# Electric_Imp_imp002_Breakout.net
KiCad netlist of a schematic drawn in EAGLE
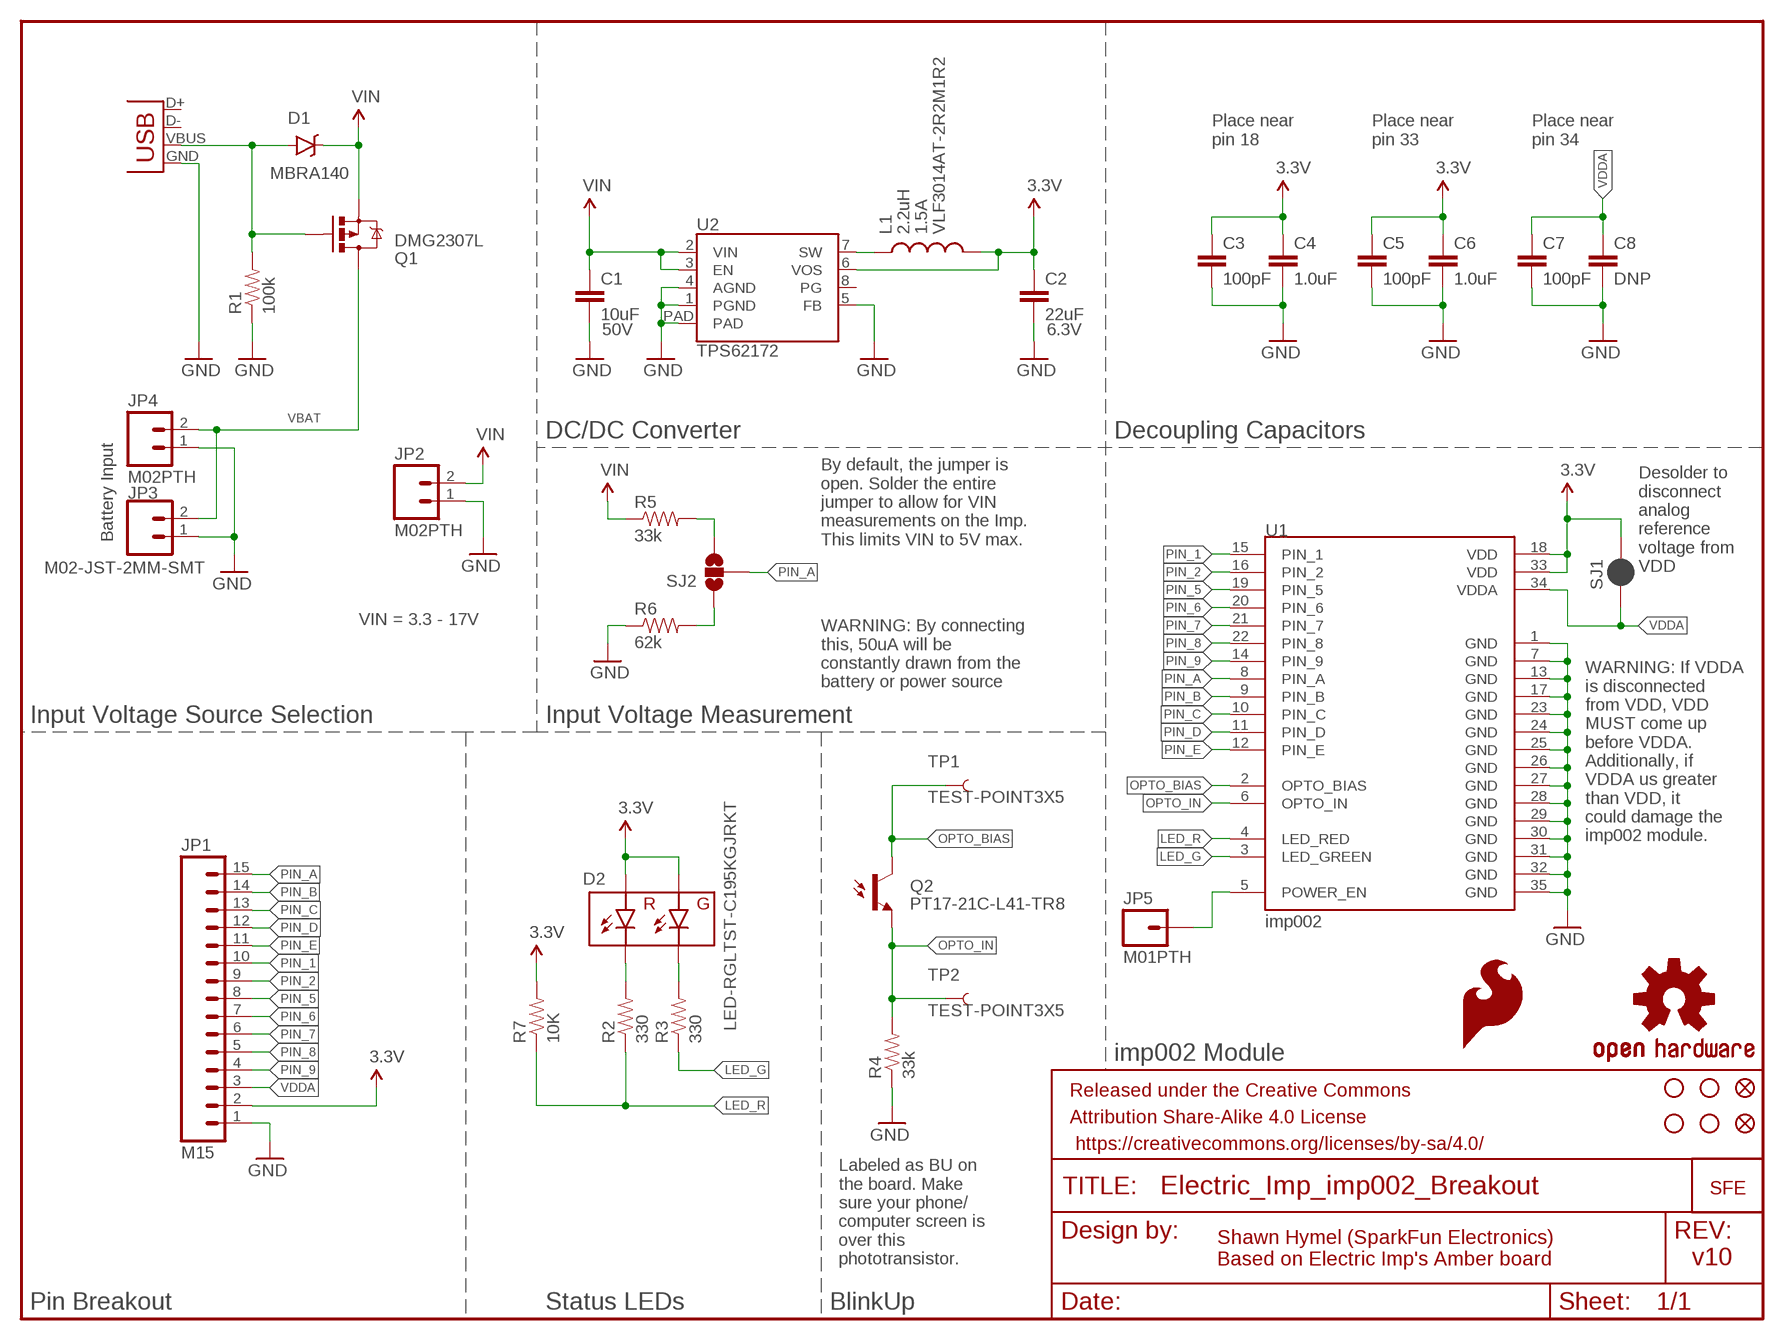
[diagram p0: schematic, sheet 1]

(export (version "E")
  (design (tool "Eeschema 10.0.6"))
  (components
    (comp (ref "C1")
      (value "10uF")
      (footprint "eagle-import:1210")
      (libsource (lib "eagle-import") (part "SparkFun-Passives_CAP1210"))
    )
    (comp (ref "C2")
      (value "22uF")
      (footprint "eagle-import:0805")
      (libsource (lib "eagle-import") (part "SparkFun-Passives_CAP0805"))
    )
    (comp (ref "C3")
      (value "100pF")
      (footprint "eagle-import:0603-CAP")
      (libsource (lib "eagle-import") (part "CAP0603-CAP"))
    )
    (comp (ref "C4")
      (value "1.0uF")
      (footprint "eagle-import:0603-CAP")
      (libsource (lib "eagle-import") (part "1.0UF-16V-10%(0603)"))
    )
    (comp (ref "C5")
      (value "100pF")
      (footprint "eagle-import:0603-CAP")
      (libsource (lib "eagle-import") (part "CAP0603-CAP"))
    )
    (comp (ref "C6")
      (value "1.0uF")
      (footprint "eagle-import:0603-CAP")
      (libsource (lib "eagle-import") (part "1.0UF-16V-10%(0603)"))
    )
    (comp (ref "C7")
      (value "100pF")
      (footprint "eagle-import:0603-CAP")
      (libsource (lib "eagle-import") (part "CAP0603-CAP"))
    )
    (comp (ref "C8")
      (value "DNP")
      (footprint "eagle-import:0603-CAP")
      (libsource (lib "eagle-import") (part "CAP0603-CAP"))
    )
    (comp (ref "D1")
      (value "MBRA140")
      (footprint "eagle-import:SMA-DIODE")
      (libsource (lib "eagle-import") (part "DIODE-SCHOTTKY-MBRA140"))
    )
    (comp (ref "D2")
      (value "LED-RGLTST-C195KGJRKT")
      (footprint "eagle-import:LTST-C195KGJRKT")
      (libsource (lib "eagle-import") (part "LED-RGLTST-C195KGJRKT"))
    )
    (comp (ref "FID1")
      (value "FIDUCIAL1X2")
      (footprint "eagle-import:FIDUCIAL-1X2")
      (libsource (lib "eagle-import") (part "FIDUCIAL1X2"))
    )
    (comp (ref "FID2")
      (value "FIDUCIAL1X2")
      (footprint "eagle-import:FIDUCIAL-1X2")
      (libsource (lib "eagle-import") (part "FIDUCIAL1X2"))
    )
    (comp (ref "FRAME1")
      (value "FRAME-LETTER")
      (footprint "eagle-import:CREATIVE_COMMONS")
      (libsource (lib "eagle-import") (part "FRAME-LETTER"))
    )
    (comp (ref "JP1")
      (value "M15")
      (footprint "eagle-import:1X15")
      (libsource (lib "eagle-import") (part "M15"))
    )
    (comp (ref "JP2")
      (value "M02PTH")
      (footprint "eagle-import:1X02")
      (libsource (lib "eagle-import") (part "M02PTH"))
    )
    (comp (ref "JP3")
      (value "M02-JST-2MM-SMT")
      (footprint "eagle-import:JST-2-SMD")
      (libsource (lib "eagle-import") (part "M02-JST-2MM-SMT"))
    )
    (comp (ref "JP4")
      (value "M02PTH")
      (footprint "eagle-import:1X02")
      (libsource (lib "eagle-import") (part "M02PTH"))
    )
    (comp (ref "JP5")
      (value "M01PTH")
      (footprint "eagle-import:1X01")
      (libsource (lib "eagle-import") (part "M01PTH"))
    )
    (comp (ref "L1")
      (value "2.2uH")
      (footprint "eagle-import:VLF4012A")
      (libsource (lib "eagle-import") (part "INDUCTORVLF4012A"))
    )
    (comp (ref "LOGO1")
      (value "OSHW-LOGOS")
      (footprint "eagle-import:OSHW-LOGO-S")
      (libsource (lib "eagle-import") (part "OSHW-LOGOS"))
    )
    (comp (ref "LOGO2")
      (value "SFE_LOGO_FLAME.1_INCH")
      (footprint "eagle-import:SFE_LOGO_FLAME_.1")
      (libsource (lib "eagle-import") (part "SFE_LOGO_FLAME.1_INCH"))
    )
    (comp (ref "Q1")
      (value "DMG2307L")
      (footprint "eagle-import:SOT23-3")
      (libsource (lib "eagle-import") (part "MOSFET-PCHANNELDMG2307L"))
    )
    (comp (ref "Q2")
      (value "PT17-21C-L41-TR8")
      (footprint "eagle-import:PT17-21C-L41-TR8")
      (libsource (lib "eagle-import") (part "PHOTOTRANSISTORPT17-21C-L41-TR8"))
    )
    (comp (ref "R1")
      (value "100k")
      (footprint "eagle-import:0603-RES")
      (libsource (lib "eagle-import") (part "100KOHM1/10W1%(0603)"))
    )
    (comp (ref "R2")
      (value "330")
      (footprint "eagle-import:0603-RES")
      (libsource (lib "eagle-import") (part "330OHM1/10W1%(0603)"))
    )
    (comp (ref "R3")
      (value "330")
      (footprint "eagle-import:0603-RES")
      (libsource (lib "eagle-import") (part "330OHM1/10W1%(0603)"))
    )
    (comp (ref "R4")
      (value "33k")
      (footprint "eagle-import:0603-RES")
      (libsource (lib "eagle-import") (part "33KOHM1/10W1%(0603)"))
    )
    (comp (ref "R5")
      (value "33k")
      (footprint "eagle-import:0603-RES")
      (libsource (lib "eagle-import") (part "33KOHM1/10W1%(0603)"))
    )
    (comp (ref "R6")
      (value "62k")
      (footprint "eagle-import:0603-RES")
      (libsource (lib "eagle-import") (part "RESISTOR0603"))
    )
    (comp (ref "R7")
      (value "10K")
      (footprint "eagle-import:0603-RES")
      (libsource (lib "eagle-import") (part "10KOHM1/10W1%(0603)0603"))
    )
    (comp (ref "SJ1")
      (value "JUMPER-PAD-2-NC_BY_PASTE")
      (footprint "eagle-import:PAD-JUMPER-2-NC_BY_PASTE_YES_SILK")
      (libsource (lib "eagle-import") (part "JUMPER-PAD-2-NC_BY_PASTE"))
    )
    (comp (ref "SJ2")
      (value "JUMPER-PAD-3-NOFULL_BOX_SILK")
      (footprint "eagle-import:PAD-JUMPER-3-NO_YES_SILK_FULL_BOX")
      (libsource (lib "eagle-import") (part "JUMPER-PAD-3-NOFULL_BOX_SILK"))
    )
    (comp (ref "STANDOFF1")
      (value "STAND-OFF")
      (footprint "eagle-import:STAND-OFF")
      (libsource (lib "eagle-import") (part "STAND-OFF"))
    )
    (comp (ref "STANDOFF2")
      (value "STAND-OFF")
      (footprint "eagle-import:STAND-OFF")
      (libsource (lib "eagle-import") (part "STAND-OFF"))
    )
    (comp (ref "STANDOFF3")
      (value "STAND-OFF")
      (footprint "eagle-import:STAND-OFF")
      (libsource (lib "eagle-import") (part "STAND-OFF"))
    )
    (comp (ref "STANDOFF4")
      (value "STAND-OFF")
      (footprint "eagle-import:STAND-OFF")
      (libsource (lib "eagle-import") (part "STAND-OFF"))
    )
    (comp (ref "TP1")
      (value "TEST-POINT3X5")
      (footprint "eagle-import:PAD.03X.05")
      (libsource (lib "eagle-import") (part "TEST-POINT3X5"))
    )
    (comp (ref "TP2")
      (value "TEST-POINT3X5")
      (footprint "eagle-import:PAD.03X.05")
      (libsource (lib "eagle-import") (part "TEST-POINT3X5"))
    )
    (comp (ref "U$9")
      (value "SFE_LOGO_NAME_WEB")
      (footprint "eagle-import:SFE-NEW-WEBLOGO")
      (libsource (lib "eagle-import") (part "SFE_LOGO_NAME_WEB"))
    )
    (comp (ref "U1")
      (value "imp002")
      (footprint "eagle-import:ELECTRIC_IMP_IMP002")
      (libsource (lib "eagle-import") (part "ELECTRIC_IMP_IMP002"))
    )
    (comp (ref "U2")
      (value "TPS62172")
      (footprint "eagle-import:WSON-8-PAD")
      (libsource (lib "eagle-import") (part "TPS62172"))
    )
    (comp (ref "X1")
      (value "USBSMD")
      (footprint "eagle-import:USB-MINIB")
      (libsource (lib "eagle-import") (part "USBSMD"))
    )
  )
  (nets
    (net (code "1") (name "/VBAT") (class "Default")
      (node (ref "JP3") (pin "2") (pinfunction "1_2") (pintype "passive"))
      (node (ref "JP4") (pin "2") (pinfunction "2_2") (pintype "passive"))
      (node (ref "Q1") (pin "3") (pinfunction "D_3") (pintype "passive"))
    )
    (net (code "2") (name "3.3V") (class "Default")
      (node (ref "C2") (pin "1") (pinfunction "1_1") (pintype "passive"))
      (node (ref "C3") (pin "1") (pinfunction "1_1") (pintype "passive"))
      (node (ref "C4") (pin "1") (pinfunction "1_1") (pintype "passive"))
      (node (ref "C5") (pin "1") (pinfunction "1_1") (pintype "passive"))
      (node (ref "C6") (pin "1") (pinfunction "1_1") (pintype "passive"))
      (node (ref "D2") (pin "P$1") (pinfunction "GA_P$1") (pintype "passive"))
      (node (ref "D2") (pin "P$2") (pinfunction "RA_P$2") (pintype "passive"))
      (node (ref "JP1") (pin "2") (pinfunction "2_2") (pintype "passive"))
      (node (ref "L1") (pin "P$2") (pinfunction "2_P$2") (pintype "passive"))
      (node (ref "R7") (pin "2") (pinfunction "2_2") (pintype "passive"))
      (node (ref "SJ1") (pin "2") (pinfunction "2_2") (pintype "passive"))
      (node (ref "U1") (pin "18") (pinfunction "VDD_18") (pintype "bidirectional"))
      (node (ref "U1") (pin "33") (pinfunction "VDD_33") (pintype "bidirectional"))
      (node (ref "U2") (pin "6") (pinfunction "VOS_6") (pintype "bidirectional"))
    )
    (net (code "3") (name "GND") (class "Default")
      (node (ref "C1") (pin "2") (pinfunction "2_2") (pintype "passive"))
      (node (ref "C2") (pin "2") (pinfunction "2_2") (pintype "passive"))
      (node (ref "C3") (pin "2") (pinfunction "2_2") (pintype "passive"))
      (node (ref "C4") (pin "2") (pinfunction "2_2") (pintype "passive"))
      (node (ref "C5") (pin "2") (pinfunction "2_2") (pintype "passive"))
      (node (ref "C6") (pin "2") (pinfunction "2_2") (pintype "passive"))
      (node (ref "C7") (pin "2") (pinfunction "2_2") (pintype "passive"))
      (node (ref "C8") (pin "2") (pinfunction "2_2") (pintype "passive"))
      (node (ref "JP1") (pin "1") (pinfunction "1_1") (pintype "passive"))
      (node (ref "JP2") (pin "1") (pinfunction "1_1") (pintype "passive"))
      (node (ref "JP3") (pin "1") (pinfunction "2_1") (pintype "passive"))
      (node (ref "JP4") (pin "1") (pinfunction "1_1") (pintype "passive"))
      (node (ref "R1") (pin "1") (pinfunction "1_1") (pintype "passive"))
      (node (ref "R4") (pin "1") (pinfunction "1_1") (pintype "passive"))
      (node (ref "R6") (pin "1") (pinfunction "1_1") (pintype "passive"))
      (node (ref "U1") (pin "1") (pinfunction "GND_1") (pintype "bidirectional"))
      (node (ref "U1") (pin "13") (pinfunction "GND_13") (pintype "bidirectional"))
      (node (ref "U1") (pin "17") (pinfunction "GND_17") (pintype "bidirectional"))
      (node (ref "U1") (pin "23") (pinfunction "GND_23") (pintype "bidirectional"))
      (node (ref "U1") (pin "24") (pinfunction "GND_24") (pintype "bidirectional"))
      (node (ref "U1") (pin "25") (pinfunction "GND_25") (pintype "bidirectional"))
      (node (ref "U1") (pin "26") (pinfunction "GND_26") (pintype "bidirectional"))
      (node (ref "U1") (pin "27") (pinfunction "GND_27") (pintype "bidirectional"))
      (node (ref "U1") (pin "28") (pinfunction "GND_28") (pintype "bidirectional"))
      (node (ref "U1") (pin "29") (pinfunction "GND_29") (pintype "bidirectional"))
      (node (ref "U1") (pin "30") (pinfunction "GND_30") (pintype "bidirectional"))
      (node (ref "U1") (pin "31") (pinfunction "GND_31") (pintype "bidirectional"))
      (node (ref "U1") (pin "32") (pinfunction "GND_32") (pintype "bidirectional"))
      (node (ref "U1") (pin "35") (pinfunction "GND_35") (pintype "bidirectional"))
      (node (ref "U1") (pin "7") (pinfunction "GND_7") (pintype "bidirectional"))
      (node (ref "U2") (pin "1") (pinfunction "PGND_1") (pintype "bidirectional"))
      (node (ref "U2") (pin "4") (pinfunction "AGND_4") (pintype "bidirectional"))
      (node (ref "U2") (pin "5") (pinfunction "FB_5") (pintype "bidirectional"))
      (node (ref "U2") (pin "PAD") (pinfunction "PAD_PAD") (pintype "bidirectional"))
      (node (ref "X1") (pin "GND") (pinfunction "GND_GND") (pintype "bidirectional"))
    )
    (net (code "4") (name "LED_G") (class "Default")
      (node (ref "R3") (pin "1") (pinfunction "1_1") (pintype "passive"))
      (node (ref "U1") (pin "3") (pinfunction "LED_GREEN_3") (pintype "bidirectional"))
    )
    (net (code "5") (name "LED_R") (class "Default")
      (node (ref "R2") (pin "1") (pinfunction "1_1") (pintype "passive"))
      (node (ref "R7") (pin "1") (pinfunction "1_1") (pintype "passive"))
      (node (ref "U1") (pin "4") (pinfunction "LED_RED_4") (pintype "bidirectional"))
    )
    (net (code "6") (name "Net-(D2-GC)") (class "Default")
      (node (ref "D2") (pin "P$3") (pinfunction "GC_P$3") (pintype "passive"))
      (node (ref "R3") (pin "2") (pinfunction "2_2") (pintype "passive"))
    )
    (net (code "7") (name "Net-(D2-RC)") (class "Default")
      (node (ref "D2") (pin "P$4") (pinfunction "RC_P$4") (pintype "passive"))
      (node (ref "R2") (pin "2") (pinfunction "2_2") (pintype "passive"))
    )
    (net (code "8") (name "Net-(L1-1)") (class "Default")
      (node (ref "L1") (pin "P$1") (pinfunction "1_P$1") (pintype "passive"))
      (node (ref "U2") (pin "7") (pinfunction "SW_7") (pintype "bidirectional"))
    )
    (net (code "9") (name "Net-(Q1-G)") (class "Default")
      (node (ref "D1") (pin "A") (pinfunction "A_A") (pintype "passive"))
      (node (ref "Q1") (pin "1") (pinfunction "G_1") (pintype "passive"))
      (node (ref "R1") (pin "2") (pinfunction "2_2") (pintype "passive"))
      (node (ref "X1") (pin "VBUS") (pinfunction "VBUS_VBUS") (pintype "bidirectional"))
    )
    (net (code "10") (name "Net-(R5-Pad2)") (class "Default")
      (node (ref "R5") (pin "2") (pinfunction "2_2") (pintype "passive"))
      (node (ref "SJ2") (pin "3") (pinfunction "3_3") (pintype "passive"))
    )
    (net (code "11") (name "Net-(R6-Pad2)") (class "Default")
      (node (ref "R6") (pin "2") (pinfunction "2_2") (pintype "passive"))
      (node (ref "SJ2") (pin "1") (pinfunction "1_1") (pintype "passive"))
    )
    (net (code "12") (name "Net-(U1-POWER_EN)") (class "Default")
      (node (ref "JP5") (pin "1") (pinfunction "1_1") (pintype "passive"))
      (node (ref "U1") (pin "5") (pinfunction "POWER_EN_5") (pintype "bidirectional"))
    )
    (net (code "13") (name "OPTO_BIAS") (class "Default")
      (node (ref "Q2") (pin "C") (pinfunction "C_C") (pintype "passive"))
      (node (ref "TP1") (pin "P$1") (pinfunction "1_P$1") (pintype "bidirectional"))
      (node (ref "U1") (pin "2") (pinfunction "OPTO_BIAS_2") (pintype "bidirectional"))
    )
    (net (code "14") (name "OPTO_IN") (class "Default")
      (node (ref "Q2") (pin "E") (pinfunction "E_E") (pintype "passive"))
      (node (ref "R4") (pin "2") (pinfunction "2_2") (pintype "passive"))
      (node (ref "TP2") (pin "P$1") (pinfunction "1_P$1") (pintype "bidirectional"))
      (node (ref "U1") (pin "6") (pinfunction "OPTO_IN_6") (pintype "bidirectional"))
    )
    (net (code "15") (name "PIN_1") (class "Default")
      (node (ref "JP1") (pin "10") (pinfunction "10_10") (pintype "passive"))
      (node (ref "U1") (pin "15") (pinfunction "PIN_1_15") (pintype "bidirectional"))
    )
    (net (code "16") (name "PIN_2") (class "Default")
      (node (ref "JP1") (pin "9") (pinfunction "9_9") (pintype "passive"))
      (node (ref "U1") (pin "16") (pinfunction "PIN_2_16") (pintype "bidirectional"))
    )
    (net (code "17") (name "PIN_5") (class "Default")
      (node (ref "JP1") (pin "8") (pinfunction "8_8") (pintype "passive"))
      (node (ref "U1") (pin "19") (pinfunction "PIN_5_19") (pintype "bidirectional"))
    )
    (net (code "18") (name "PIN_6") (class "Default")
      (node (ref "JP1") (pin "7") (pinfunction "7_7") (pintype "passive"))
      (node (ref "U1") (pin "20") (pinfunction "PIN_6_20") (pintype "bidirectional"))
    )
    (net (code "19") (name "PIN_7") (class "Default")
      (node (ref "JP1") (pin "6") (pinfunction "6_6") (pintype "passive"))
      (node (ref "U1") (pin "21") (pinfunction "PIN_7_21") (pintype "bidirectional"))
    )
    (net (code "20") (name "PIN_8") (class "Default")
      (node (ref "JP1") (pin "5") (pinfunction "5_5") (pintype "passive"))
      (node (ref "U1") (pin "22") (pinfunction "PIN_8_22") (pintype "bidirectional"))
    )
    (net (code "21") (name "PIN_9") (class "Default")
      (node (ref "JP1") (pin "4") (pinfunction "4_4") (pintype "passive"))
      (node (ref "U1") (pin "14") (pinfunction "PIN_9_14") (pintype "bidirectional"))
    )
    (net (code "22") (name "PIN_A") (class "Default")
      (node (ref "JP1") (pin "15") (pinfunction "15_15") (pintype "passive"))
      (node (ref "SJ2") (pin "2") (pinfunction "2_2") (pintype "passive"))
      (node (ref "U1") (pin "8") (pinfunction "PIN_A_8") (pintype "bidirectional"))
    )
    (net (code "23") (name "PIN_B") (class "Default")
      (node (ref "JP1") (pin "14") (pinfunction "14_14") (pintype "passive"))
      (node (ref "U1") (pin "9") (pinfunction "PIN_B_9") (pintype "bidirectional"))
    )
    (net (code "24") (name "PIN_C") (class "Default")
      (node (ref "JP1") (pin "13") (pinfunction "13_13") (pintype "passive"))
      (node (ref "U1") (pin "10") (pinfunction "PIN_C_10") (pintype "bidirectional"))
    )
    (net (code "25") (name "PIN_D") (class "Default")
      (node (ref "JP1") (pin "12") (pinfunction "12_12") (pintype "passive"))
      (node (ref "U1") (pin "11") (pinfunction "PIN_D_11") (pintype "bidirectional"))
    )
    (net (code "26") (name "PIN_E") (class "Default")
      (node (ref "JP1") (pin "11") (pinfunction "11_11") (pintype "passive"))
      (node (ref "U1") (pin "12") (pinfunction "PIN_E_12") (pintype "bidirectional"))
    )
    (net (code "27") (name "VDDA") (class "Default")
      (node (ref "C7") (pin "1") (pinfunction "1_1") (pintype "passive"))
      (node (ref "C8") (pin "1") (pinfunction "1_1") (pintype "passive"))
      (node (ref "JP1") (pin "3") (pinfunction "3_3") (pintype "passive"))
      (node (ref "SJ1") (pin "1") (pinfunction "1_1") (pintype "passive"))
      (node (ref "U1") (pin "34") (pinfunction "VDDA_34") (pintype "bidirectional"))
    )
    (net (code "28") (name "VIN") (class "Default")
      (node (ref "C1") (pin "1") (pinfunction "1_1") (pintype "passive"))
      (node (ref "D1") (pin "C") (pinfunction "C_C") (pintype "passive"))
      (node (ref "JP2") (pin "2") (pinfunction "2_2") (pintype "passive"))
      (node (ref "Q1") (pin "2") (pinfunction "S_2") (pintype "passive"))
      (node (ref "R5") (pin "1") (pinfunction "1_1") (pintype "passive"))
      (node (ref "U2") (pin "2") (pinfunction "VIN_2") (pintype "bidirectional"))
      (node (ref "U2") (pin "3") (pinfunction "EN_3") (pintype "bidirectional"))
    )
    (net (code "29") (name "unconnected-(U2-PG-Pad8)") (class "Default")
      (node (ref "U2") (pin "8") (pinfunction "PG_8") (pintype "bidirectional"))
    )
    (net (code "30") (name "unconnected-(X1-PadD+)") (class "Default")
      (node (ref "X1") (pin "D+") (pinfunction "D+_D+") (pintype "bidirectional"))
    )
    (net (code "31") (name "unconnected-(X1-PadD-)") (class "Default")
      (node (ref "X1") (pin "D-") (pinfunction "D-_D-") (pintype "bidirectional"))
    )
  )
)
